# LCD_shift_register_Attiny85.net
KiCad netlist of a schematic drawn in EAGLE
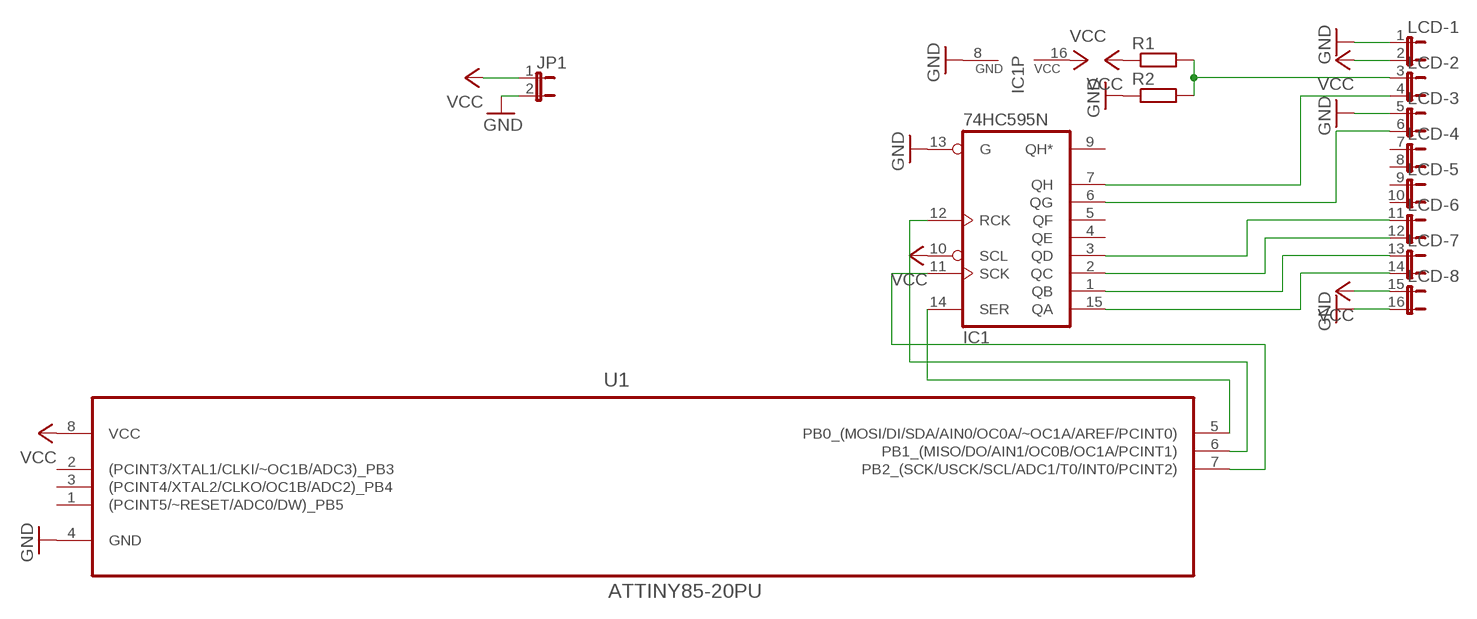
[diagram p0: schematic, sheet 1]

(export (version "E")
  (design (tool "Eeschema 10.0.6"))
  (components
    (comp (ref "IC1")
      (value "74HC595N")
      (footprint "eagle-import:DIL16")
      (libsource (lib "eagle-import") (part "74595NHC"))
    )
    (comp (ref "JP1")
      (value "JP1E")
      (footprint "eagle-import:JP1")
      (libsource (lib "eagle-import") (part "JP1E"))
    )
    (comp (ref "LCD")
      (value "JP8QE")
      (footprint "eagle-import:JP8Q")
      (libsource (lib "eagle-import") (part "JP8QE"))
    )
    (comp (ref "R1")
      (value "R-EU_0207/10")
      (footprint "eagle-import:0207_10")
      (libsource (lib "eagle-import") (part "R-EU_0207/10"))
    )
    (comp (ref "R2")
      (value "R-EU_0207/10")
      (footprint "eagle-import:0207_10")
      (libsource (lib "eagle-import") (part "R-EU_0207/10"))
    )
    (comp (ref "U1")
      (value "ATTINY85-20PU")
      (footprint "eagle-import:DIP254P762X533-8")
      (libsource (lib "eagle-import") (part "ATTINY85-20PU"))
    )
  )
  (nets
    (net (code "1") (name "GND") (class "Default")
      (node (ref "IC1") (pin "13") (pinfunction "G_13") (pintype "input"))
      (node (ref "IC1") (pin "8") (pinfunction "GND_8") (pintype "power_in"))
      (node (ref "JP1") (pin "2") (pinfunction "2_2") (pintype "passive"))
      (node (ref "LCD") (pin "1") (pinfunction "1_1") (pintype "passive"))
      (node (ref "LCD") (pin "16") (pinfunction "2_16") (pintype "passive"))
      (node (ref "LCD") (pin "5") (pinfunction "1_5") (pintype "passive"))
      (node (ref "R2") (pin "1") (pinfunction "1_1") (pintype "passive"))
      (node (ref "U1") (pin "4") (pinfunction "GND_4") (pintype "passive"))
    )
    (net (code "2") (name "Net-(IC1A-QA)") (class "Default")
      (node (ref "IC1") (pin "15") (pinfunction "QA_15") (pintype "tri_state"))
      (node (ref "LCD") (pin "14") (pinfunction "2_14") (pintype "passive"))
    )
    (net (code "3") (name "Net-(IC1A-QB)") (class "Default")
      (node (ref "IC1") (pin "1") (pinfunction "QB_1") (pintype "tri_state"))
      (node (ref "LCD") (pin "13") (pinfunction "1_13") (pintype "passive"))
    )
    (net (code "4") (name "Net-(IC1A-QC)") (class "Default")
      (node (ref "IC1") (pin "2") (pinfunction "QC_2") (pintype "tri_state"))
      (node (ref "LCD") (pin "12") (pinfunction "2_12") (pintype "passive"))
    )
    (net (code "5") (name "Net-(IC1A-QD)") (class "Default")
      (node (ref "IC1") (pin "3") (pinfunction "QD_3") (pintype "tri_state"))
      (node (ref "LCD") (pin "11") (pinfunction "1_11") (pintype "passive"))
    )
    (net (code "6") (name "Net-(IC1A-QG)") (class "Default")
      (node (ref "IC1") (pin "6") (pinfunction "QG_6") (pintype "tri_state"))
      (node (ref "LCD") (pin "6") (pinfunction "2_6") (pintype "passive"))
    )
    (net (code "7") (name "Net-(IC1A-QH)") (class "Default")
      (node (ref "IC1") (pin "7") (pinfunction "QH_7") (pintype "tri_state"))
      (node (ref "LCD") (pin "4") (pinfunction "2_4") (pintype "passive"))
    )
    (net (code "8") (name "Net-(IC1A-RCK)") (class "Default")
      (node (ref "IC1") (pin "12") (pinfunction "RCK_12") (pintype "input"))
      (node (ref "U1") (pin "6") (pinfunction "PB1_(MISO/DO/AIN1/OC0B/OC1A/PCINT1)_6") (pintype "bidirectional"))
    )
    (net (code "9") (name "Net-(IC1A-SCK)") (class "Default")
      (node (ref "IC1") (pin "11") (pinfunction "SCK_11") (pintype "input"))
      (node (ref "U1") (pin "7") (pinfunction "PB2_(SCK/USCK/SCL/ADC1/T0/INT0/PCINT2)_7") (pintype "bidirectional"))
    )
    (net (code "10") (name "Net-(IC1A-SER)") (class "Default")
      (node (ref "IC1") (pin "14") (pinfunction "SER_14") (pintype "input"))
      (node (ref "U1") (pin "5") (pinfunction "PB0_(MOSI/DI/SDA/AIN0/OC0A/~{OC1A/AREF/PCINT0})_5") (pintype "bidirectional"))
    )
    (net (code "11") (name "Net-(LCDB-1)") (class "Default")
      (node (ref "LCD") (pin "3") (pinfunction "1_3") (pintype "passive"))
      (node (ref "R1") (pin "2") (pinfunction "2_2") (pintype "passive"))
      (node (ref "R2") (pin "2") (pinfunction "2_2") (pintype "passive"))
    )
    (net (code "12") (name "VCC") (class "Default")
      (node (ref "IC1") (pin "10") (pinfunction "SCL_10") (pintype "input"))
      (node (ref "IC1") (pin "16") (pinfunction "VCC_16") (pintype "power_in"))
      (node (ref "JP1") (pin "1") (pinfunction "1_1") (pintype "passive"))
      (node (ref "LCD") (pin "15") (pinfunction "1_15") (pintype "passive"))
      (node (ref "LCD") (pin "2") (pinfunction "2_2") (pintype "passive"))
      (node (ref "R1") (pin "1") (pinfunction "1_1") (pintype "passive"))
      (node (ref "U1") (pin "8") (pinfunction "VCC_8") (pintype "power_in"))
    )
    (net (code "13") (name "unconnected-(IC1A-QE-Pad4)") (class "Default")
      (node (ref "IC1") (pin "4") (pinfunction "QE_4") (pintype "tri_state"))
    )
    (net (code "14") (name "unconnected-(IC1A-QF-Pad5)") (class "Default")
      (node (ref "IC1") (pin "5") (pinfunction "QF_5") (pintype "tri_state"))
    )
    (net (code "15") (name "unconnected-(IC1A-QH*-Pad9)") (class "Default")
      (node (ref "IC1") (pin "9") (pinfunction "QH*_9") (pintype "tri_state"))
    )
    (net (code "16") (name "unconnected-(LCDD-1-Pad7)") (class "Default")
      (node (ref "LCD") (pin "7") (pinfunction "1_7") (pintype "passive"))
    )
    (net (code "17") (name "unconnected-(LCDD-2-Pad8)") (class "Default")
      (node (ref "LCD") (pin "8") (pinfunction "2_8") (pintype "passive"))
    )
    (net (code "18") (name "unconnected-(LCDE-1-Pad9)") (class "Default")
      (node (ref "LCD") (pin "9") (pinfunction "1_9") (pintype "passive"))
    )
    (net (code "19") (name "unconnected-(LCDE-2-Pad10)") (class "Default")
      (node (ref "LCD") (pin "10") (pinfunction "2_10") (pintype "passive"))
    )
    (net (code "20") (name "unconnected-(U1-(PCINT3{slash}XTAL1{slash}CLKI{slash}~{OC1B{slash}ADC3})_PB3-Pad2)") (class "Default")
      (node (ref "U1") (pin "2") (pinfunction "(PCINT3/XTAL1/CLKI/~{OC1B/ADC3})_PB3_2") (pintype "bidirectional"))
    )
    (net (code "21") (name "unconnected-(U1-(PCINT4{slash}XTAL2{slash}CLKO{slash}OC1B{slash}ADC2)_PB4-Pad3)") (class "Default")
      (node (ref "U1") (pin "3") (pinfunction "(PCINT4/XTAL2/CLKO/OC1B/ADC2)_PB4_3") (pintype "bidirectional"))
    )
    (net (code "22") (name "unconnected-(U1-(PCINT5{slash}~{RESET{slash}ADC0{slash}DW})_PB5-Pad1)") (class "Default")
      (node (ref "U1") (pin "1") (pinfunction "(PCINT5/~{RESET/ADC0/DW})_PB5_1") (pintype "bidirectional"))
    )
  )
)
